# Motor_Controller_V_5_2.net
KiCad netlist of a schematic drawn in EAGLE
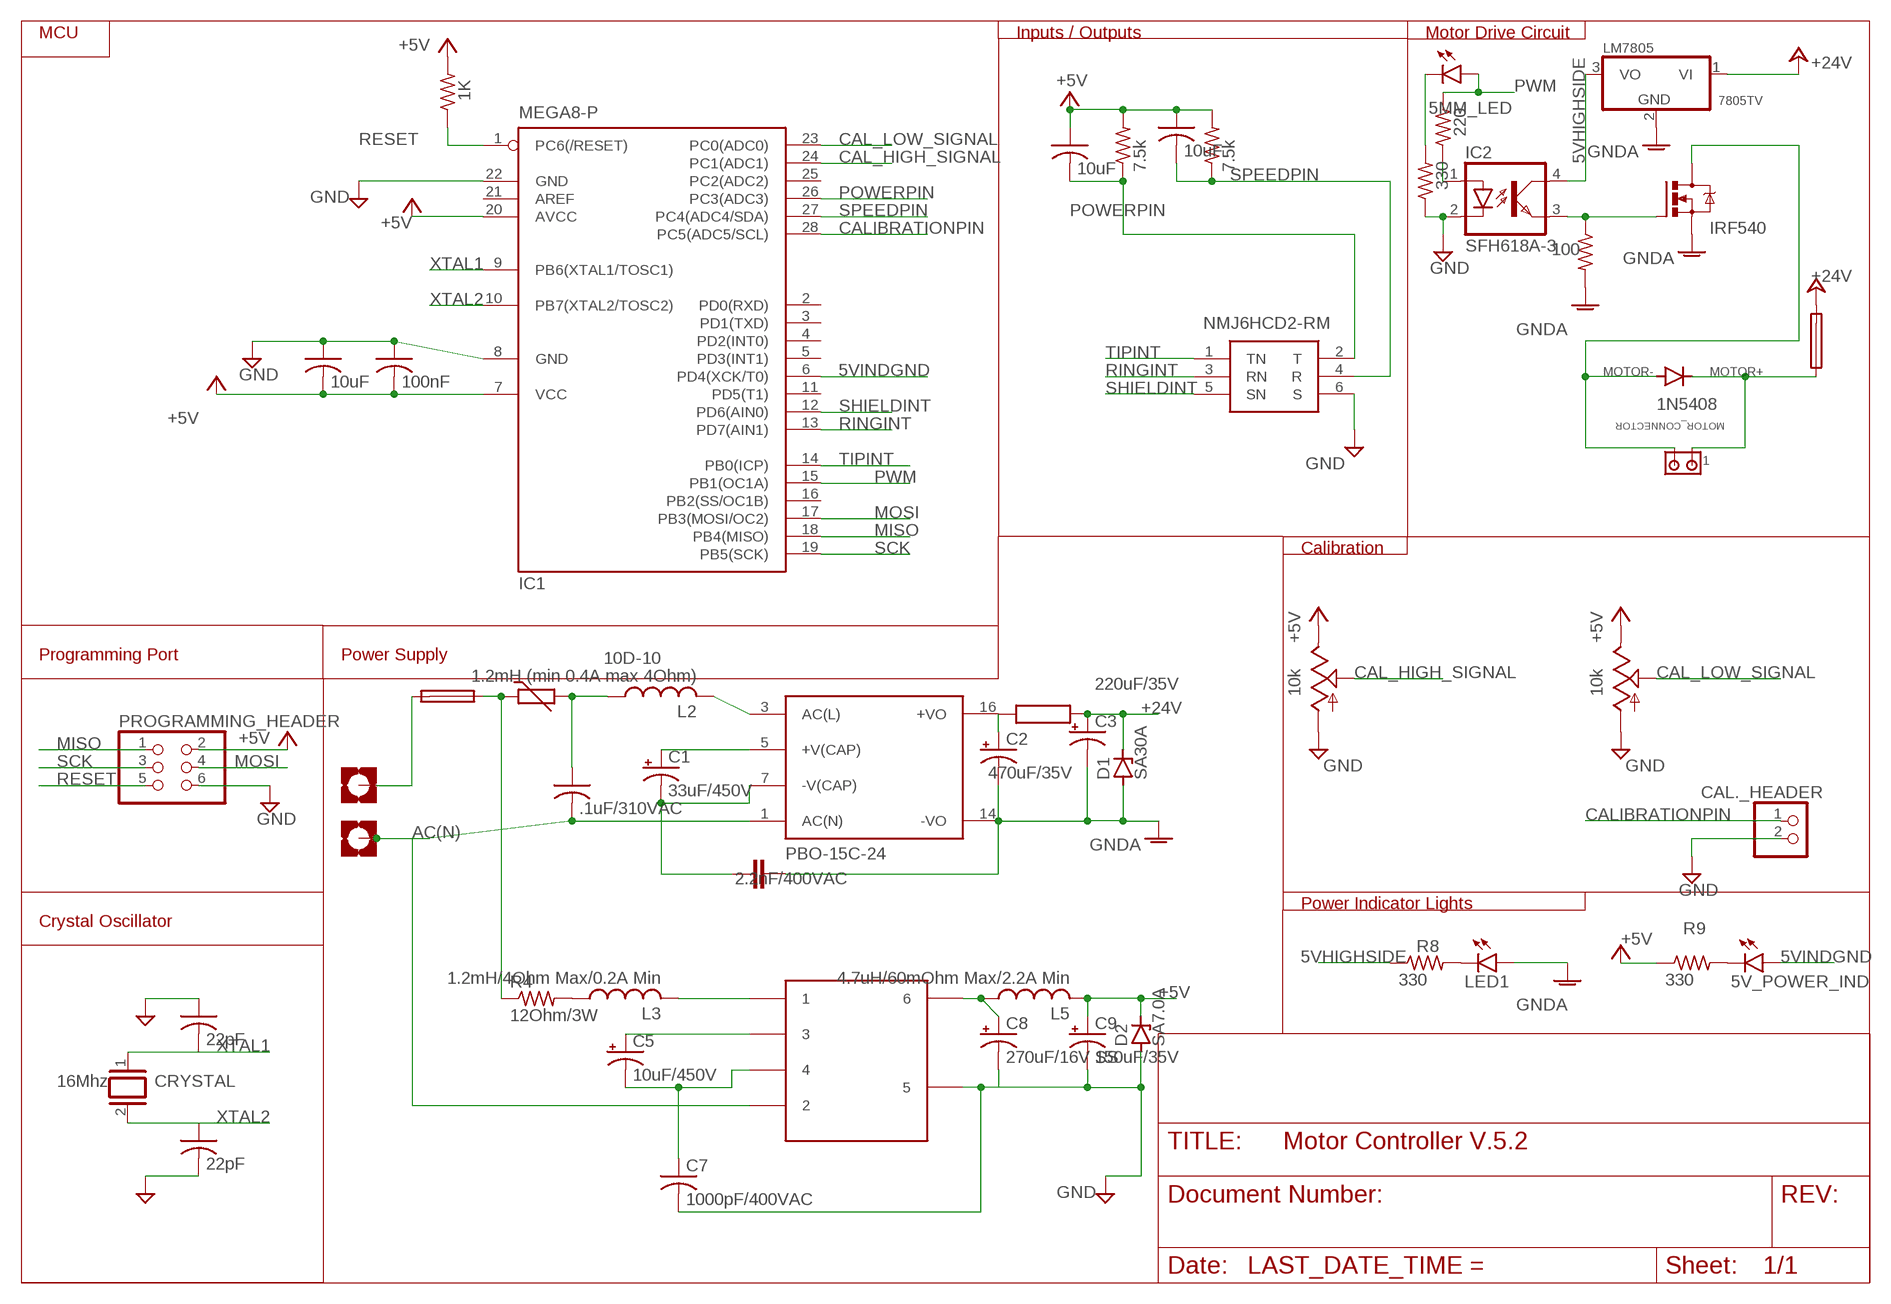
[diagram p0: schematic, sheet 1]

(export (version "E")
  (design (tool "Eeschema 10.0.6"))
  (components
    (comp (ref "5V_POWER_IND")
      (value "LED3MM")
      (footprint "eagle-import:LED3MM")
      (libsource (lib "eagle-import") (part "LED3MM"))
    )
    (comp (ref "AC(N)")
      (value "PAD3.0")
      (footprint "eagle-import:3,0-PAD-SQUARE")
      (libsource (lib "eagle-import") (part "PAD3.0"))
    )
    (comp (ref "C1")
      (value "33uF/450V")
      (footprint "eagle-import:E5-13")
      (libsource (lib "eagle-import") (part "CPOL-USE5-13"))
    )
    (comp (ref "C2")
      (value "470uF/35V")
      (footprint "eagle-import:E5-10,5")
      (fields (field (name "MF") "PANASONIC") (field (name "MPN") "ECA1VHG471B"))
      (libsource (lib "eagle-import") (part "CPOL-USE5-10.5"))
    )
    (comp (ref "C3")
      (value "220uF/35V")
      (footprint "eagle-import:E5-10,5")
      (fields (field (name "MF") "KEMET") (field (name "MPN") "A768KS227M1VLAE024"))
      (libsource (lib "eagle-import") (part "CPOL-USE5-10.5"))
    )
    (comp (ref "C4")
      (value ".1uF/310VAC")
      (footprint "eagle-import:C102-064X133")
      (libsource (lib "eagle-import") (part "CMPP_AC275V104K10S6"))
    )
    (comp (ref "C5")
      (value "10uF/450V")
      (footprint "eagle-import:E5-10,5")
      (libsource (lib "eagle-import") (part "CPOL-USE5-10.5"))
    )
    (comp (ref "C6")
      (value "22pF")
      (footprint "eagle-import:C025-024X044")
      (libsource (lib "eagle-import") (part "C-US025-024X044"))
    )
    (comp (ref "C7")
      (value "1000pF/400VAC")
      (footprint "eagle-import:C075-052X106")
      (libsource (lib "eagle-import") (part "C-US075-052X106"))
    )
    (comp (ref "C8")
      (value "270uF/16V SS")
      (footprint "eagle-import:E2,5-6")
      (libsource (lib "eagle-import") (part "CPOL-USE2.5-6"))
    )
    (comp (ref "C9")
      (value "150uF/35V")
      (footprint "eagle-import:E3,5-8")
      (libsource (lib "eagle-import") (part "CPOL-USE3.5-8"))
    )
    (comp (ref "C10")
      (value "10uF")
      (footprint "eagle-import:C025-024X044")
      (libsource (lib "eagle-import") (part "C-US025-024X044"))
    )
    (comp (ref "C12")
      (value "10uF")
      (footprint "eagle-import:C025-024X044")
      (libsource (lib "eagle-import") (part "C-US025-024X044"))
    )
    (comp (ref "C13")
      (value "10uF")
      (footprint "eagle-import:C025-024X044")
      (libsource (lib "eagle-import") (part "C-US025-024X044"))
    )
    (comp (ref "C14")
      (value "100nF")
      (footprint "eagle-import:C025-024X044")
      (libsource (lib "eagle-import") (part "C-US025-024X044"))
    )
    (comp (ref "C15")
      (value "22pF")
      (footprint "eagle-import:C025-024X044")
      (libsource (lib "eagle-import") (part "C-US025-024X044"))
    )
    (comp (ref "CAL._HEADER")
      (value "PINHD-1X2")
      (footprint "eagle-import:1X02")
      (libsource (lib "eagle-import") (part "PINHD-1X2"))
    )
    (comp (ref "CRYSTAL")
      (value "16Mhz")
      (footprint "eagle-import:QS")
      (libsource (lib "eagle-import") (part "XTAL/S"))
    )
    (comp (ref "CY1")
      (value "2.2nF/400VAC")
      (footprint "eagle-import:YC10B4")
      (libsource (lib "eagle-import") (part "CYYC10B4"))
    )
    (comp (ref "D1")
      (value "SA30A")
      (footprint "eagle-import:TVS-10")
      (libsource (lib "eagle-import") (part "TVSDIO"))
    )
    (comp (ref "D2")
      (value "SA7.0A")
      (footprint "eagle-import:TVS-10")
      (libsource (lib "eagle-import") (part "TVSDIO"))
    )
    (comp (ref "D3")
      (value "1N5408")
      (footprint "eagle-import:DO201-15")
      (fields (field (name "MF") "VISHAY") (field (name "MPN") "1N5408-E3/54"))
      (libsource (lib "eagle-import") (part "1N5400"))
    )
    (comp (ref "F1")
      (value "FUSESH22,5")
      (footprint "eagle-import:SH22,5")
      (libsource (lib "eagle-import") (part "FUSESH22,5"))
    )
    (comp (ref "F2")
      (value "1A/300V")
      (footprint "eagle-import:SH22,5")
      (libsource (lib "eagle-import") (part "FUSESH22,5"))
    )
    (comp (ref "FAST")
      (value "10k")
      (footprint "eagle-import:CT6")
      (libsource (lib "eagle-import") (part "TRIM_US-CT6"))
    )
    (comp (ref "H1")
      (value "PAD3.0")
      (footprint "eagle-import:3,0-PAD-SQUARE")
      (libsource (lib "eagle-import") (part "PAD3.0"))
    )
    (comp (ref "IC1")
      (value "MEGA8-P")
      (footprint "eagle-import:DIL28-3")
      (libsource (lib "eagle-import") (part "MEGA8-P"))
    )
    (comp (ref "IC2")
      (value "SFH618A-3")
      (footprint "eagle-import:DIP4")
      (fields (field (name "MF") "VISHAY/TELEFUNKEN"))
      (libsource (lib "eagle-import") (part "SFH618?A-3"))
    )
    (comp (ref "J1")
      (value "NMJ6HCD2-RM")
      (footprint "eagle-import:NMJ6HCD2RM")
      (fields (field (name "MOUSER_PART_NUMBER") "568-NMJ6HCD2-RM"))
      (libsource (lib "eagle-import") (part "NMJ6HCD2-RM"))
    )
    (comp (ref "L2")
      (value "1.2mH (min 0.4A max 4Ohm)")
      (footprint "eagle-import:RCP1317_INDUCTOR")
      (libsource (lib "eagle-import") (part "RCP_1317_INDUCTOR"))
    )
    (comp (ref "L3")
      (value "1.2mH/4Ohm Max/0.2A Min")
      (footprint "eagle-import:RCP1317_INDUCTOR")
      (libsource (lib "eagle-import") (part "RCP_1317_INDUCTOR"))
    )
    (comp (ref "L5")
      (value "4.7uH/60mOhm Max/2.2A Min")
      (footprint "eagle-import:RLB0914_INDUCTOR")
      (libsource (lib "eagle-import") (part "RLB0914_INDUCTOR"))
    )
    (comp (ref "LED1")
      (value "LED3MM")
      (footprint "eagle-import:LED3MM")
      (libsource (lib "eagle-import") (part "LED3MM"))
    )
    (comp (ref "LM7805")
      (value "7805TV")
      (footprint "eagle-import:TO220V")
      (libsource (lib "eagle-import") (part "78TV05"))
    )
    (comp (ref "MOTOR_CONNECTOR")
      (value "MATE-N-LOK_193839-1")
      (footprint "eagle-import:MATE-N-LOK_2PIN_CONNECTOR")
      (libsource (lib "eagle-import") (part "MATE-N-LOK_193839-1"))
    )
    (comp (ref "PROGRAMMING_HEADER")
      (value "PINHD-2X3")
      (footprint "eagle-import:2X03")
      (libsource (lib "eagle-import") (part "PINHD-2X3"))
    )
    (comp (ref "PS1")
      (value "PBO-15C-24")
      (footprint "eagle-import:CONV_PBO-15C-24")
      (fields (field (name "MF") "CUI Inc."))
      (libsource (lib "eagle-import") (part "PBO-15C-24"))
    )
    (comp (ref "PWM_IND")
      (value "5MM_LED")
      (footprint "eagle-import:5MM_LED")
      (libsource (lib "eagle-import") (part "5MM_LED"))
    )
    (comp (ref "Q1")
      (value "IRF540")
      (footprint "eagle-import:TO220BV")
      (libsource (lib "eagle-import") (part "IRF540"))
    )
    (comp (ref "R1")
      (value "10D-10")
      (footprint "eagle-import:R-7,5")
      (libsource (lib "eagle-import") (part "THERMISTOR-7,5"))
    )
    (comp (ref "R2")
      (value "1K")
      (footprint "eagle-import:0204_7")
      (libsource (lib "eagle-import") (part "R-US_0204/7"))
    )
    (comp (ref "R3")
      (value "7.5k")
      (footprint "eagle-import:0204_7")
      (libsource (lib "eagle-import") (part "R-US_0204/7"))
    )
    (comp (ref "R4")
      (value "12Ohm/3W")
      (footprint "eagle-import:VTA52")
      (libsource (lib "eagle-import") (part "BIGRESISTOR"))
    )
    (comp (ref "R5")
      (value "220")
      (footprint "eagle-import:0204_7")
      (libsource (lib "eagle-import") (part "R-US_0204/7"))
    )
    (comp (ref "R6")
      (value "100")
      (footprint "eagle-import:0204_7")
      (libsource (lib "eagle-import") (part "R-US_0204/7"))
    )
    (comp (ref "R7")
      (value "7.5k")
      (footprint "eagle-import:0204_7")
      (libsource (lib "eagle-import") (part "R-US_0204/7"))
    )
    (comp (ref "R8")
      (value "330")
      (footprint "eagle-import:0204_7")
      (libsource (lib "eagle-import") (part "R-US_0204/7"))
    )
    (comp (ref "R9")
      (value "330")
      (footprint "eagle-import:0204_7")
      (libsource (lib "eagle-import") (part "R-US_0204/7"))
    )
    (comp (ref "R10")
      (value "330")
      (footprint "eagle-import:0204_7")
      (libsource (lib "eagle-import") (part "R-US_0204/7"))
    )
    (comp (ref "SLOW")
      (value "10k")
      (footprint "eagle-import:CT6")
      (libsource (lib "eagle-import") (part "TRIM_US-CT6"))
    )
    (comp (ref "U$1")
      (value "L503-13B05R")
      (footprint "eagle-import:LS03-13BO5R3")
      (libsource (lib "eagle-import") (part "L503-13B05R"))
    )
    (comp (ref "U$2")
      (value "HCTI-22-16.4")
      (footprint "eagle-import:HCTI-22-16.4")
      (libsource (lib "eagle-import") (part "HCTI-22-16.4"))
    )
  )
  (nets
    (net (code "1") (name "+5V") (class "Default")
      (node (ref "C10") (pin "1") (pinfunction "1_1") (pintype "passive"))
      (node (ref "C12") (pin "1") (pinfunction "1_1") (pintype "passive"))
      (node (ref "C13") (pin "2") (pinfunction "2_2") (pintype "passive"))
      (node (ref "C14") (pin "2") (pinfunction "2_2") (pintype "passive"))
      (node (ref "C9") (pin "+") (pinfunction "+_+") (pintype "passive"))
      (node (ref "D2") (pin "C") (pinfunction "C_C") (pintype "passive"))
      (node (ref "FAST") (pin "E") (pinfunction "E_E") (pintype "passive"))
      (node (ref "IC1") (pin "20") (pinfunction "AVCC_20") (pintype "power_in"))
      (node (ref "IC1") (pin "7") (pinfunction "VCC_7") (pintype "power_in"))
      (node (ref "L5") (pin "P$2") (pinfunction "2_P$2") (pintype "passive"))
      (node (ref "PROGRAMMING_HEADER") (pin "2") (pinfunction "2_2") (pintype "passive"))
      (node (ref "R2") (pin "2") (pinfunction "2_2") (pintype "passive"))
      (node (ref "R3") (pin "2") (pinfunction "2_2") (pintype "passive"))
      (node (ref "R7") (pin "2") (pinfunction "2_2") (pintype "passive"))
      (node (ref "R9") (pin "1") (pinfunction "1_1") (pintype "passive"))
      (node (ref "SLOW") (pin "E") (pinfunction "E_E") (pintype "passive"))
    )
    (net (code "2") (name "+24V") (class "Default")
      (node (ref "C3") (pin "+") (pinfunction "+_+") (pintype "passive"))
      (node (ref "D1") (pin "C") (pinfunction "C_C") (pintype "passive"))
      (node (ref "F1") (pin "2") (pinfunction "2_2") (pintype "passive"))
      (node (ref "LM7805") (pin "1") (pinfunction "VI_1") (pintype "input"))
      (node (ref "U$2") (pin "P$2") (pinfunction "P$2_P$2") (pintype "bidirectional"))
    )
    (net (code "3") (name "/5VHIGHSIDE") (class "Default")
      (node (ref "IC2") (pin "4") (pinfunction "COL_4") (pintype "passive"))
      (node (ref "LM7805") (pin "3") (pinfunction "VO_3") (pintype "passive"))
      (node (ref "R8") (pin "1") (pinfunction "1_1") (pintype "passive"))
    )
    (net (code "4") (name "/5VINDGND") (class "Default")
      (node (ref "5V_POWER_IND") (pin "A") (pinfunction "A_A") (pintype "passive"))
      (node (ref "IC1") (pin "6") (pinfunction "PD4(XCK/T0)_6") (pintype "bidirectional"))
    )
    (net (code "5") (name "/AC(N)") (class "Default")
      (node (ref "AC(N)") (pin "B3,0") (pinfunction "MOUNT_B3,0") (pintype "passive"))
      (node (ref "C4") (pin "2") (pinfunction "2_2") (pintype "passive"))
      (node (ref "PS1") (pin "1") (pinfunction "AC(N)_1") (pintype "input"))
      (node (ref "U$1") (pin "3") (pinfunction "2_3") (pintype "bidirectional"))
      (node (ref "U$1") (pin "4") (pinfunction "2_4") (pintype "bidirectional"))
    )
    (net (code "6") (name "/CALIBRATIONPIN") (class "Default")
      (node (ref "CAL._HEADER") (pin "1") (pinfunction "1_1") (pintype "passive"))
      (node (ref "IC1") (pin "28") (pinfunction "PC5(ADC5/SCL)_28") (pintype "bidirectional"))
    )
    (net (code "7") (name "/CAL_HIGH_SIGNAL") (class "Default")
      (node (ref "FAST") (pin "S") (pinfunction "S_S") (pintype "passive"))
      (node (ref "IC1") (pin "24") (pinfunction "PC1(ADC1)_24") (pintype "bidirectional"))
    )
    (net (code "8") (name "/CAL_LOW_SIGNAL") (class "Default")
      (node (ref "IC1") (pin "23") (pinfunction "PC0(ADC0)_23") (pintype "bidirectional"))
      (node (ref "SLOW") (pin "S") (pinfunction "S_S") (pintype "passive"))
    )
    (net (code "9") (name "/MISO") (class "Default")
      (node (ref "IC1") (pin "18") (pinfunction "PB4(MISO)_18") (pintype "bidirectional"))
      (node (ref "PROGRAMMING_HEADER") (pin "1") (pinfunction "1_1") (pintype "passive"))
    )
    (net (code "10") (name "/MOSI") (class "Default")
      (node (ref "IC1") (pin "17") (pinfunction "PB3(MOSI/OC2)_17") (pintype "bidirectional"))
      (node (ref "PROGRAMMING_HEADER") (pin "4") (pinfunction "4_4") (pintype "passive"))
    )
    (net (code "11") (name "/MOTOR+") (class "Default")
      (node (ref "D3") (pin "C") (pinfunction "C_C") (pintype "passive"))
      (node (ref "F1") (pin "1") (pinfunction "1_1") (pintype "passive"))
      (node (ref "MOTOR_CONNECTOR") (pin "P$1") (pinfunction "1_P$1") (pintype "passive"))
    )
    (net (code "12") (name "/MOTOR-") (class "Default")
      (node (ref "D3") (pin "A") (pinfunction "A_A") (pintype "passive"))
      (node (ref "MOTOR_CONNECTOR") (pin "P$2") (pinfunction "2_P$2") (pintype "passive"))
      (node (ref "Q1") (pin "D") (pinfunction "D_D") (pintype "passive"))
    )
    (net (code "13") (name "/POWERPIN") (class "Default")
      (node (ref "C10") (pin "2") (pinfunction "2_2") (pintype "passive"))
      (node (ref "IC1") (pin "26") (pinfunction "PC3(ADC3)_26") (pintype "bidirectional"))
      (node (ref "J1") (pin "2") (pinfunction "T_2") (pintype "bidirectional"))
      (node (ref "R3") (pin "1") (pinfunction "1_1") (pintype "passive"))
    )
    (net (code "14") (name "/PWM") (class "Default")
      (node (ref "IC1") (pin "15") (pinfunction "PB1(OC1A)_15") (pintype "bidirectional"))
      (node (ref "PWM_IND") (pin "A") (pinfunction "A_A") (pintype "passive"))
      (node (ref "R5") (pin "2") (pinfunction "2_2") (pintype "passive"))
    )
    (net (code "15") (name "/RESET") (class "Default")
      (node (ref "IC1") (pin "1") (pinfunction "PC6(/RESET)_1") (pintype "bidirectional"))
      (node (ref "PROGRAMMING_HEADER") (pin "5") (pinfunction "5_5") (pintype "passive"))
      (node (ref "R2") (pin "1") (pinfunction "1_1") (pintype "passive"))
    )
    (net (code "16") (name "/RINGINT") (class "Default")
      (node (ref "IC1") (pin "13") (pinfunction "PD7(AIN1)_13") (pintype "bidirectional"))
      (node (ref "J1") (pin "3") (pinfunction "RN_3") (pintype "bidirectional"))
    )
    (net (code "17") (name "/SCK") (class "Default")
      (node (ref "IC1") (pin "19") (pinfunction "PB5(SCK)_19") (pintype "bidirectional"))
      (node (ref "PROGRAMMING_HEADER") (pin "3") (pinfunction "3_3") (pintype "passive"))
    )
    (net (code "18") (name "/SHIELDINT") (class "Default")
      (node (ref "IC1") (pin "12") (pinfunction "PD6(AIN0)_12") (pintype "bidirectional"))
      (node (ref "J1") (pin "5") (pinfunction "SN_5") (pintype "bidirectional"))
    )
    (net (code "19") (name "/SPEEDPIN") (class "Default")
      (node (ref "C12") (pin "2") (pinfunction "2_2") (pintype "passive"))
      (node (ref "IC1") (pin "27") (pinfunction "PC4(ADC4/SDA)_27") (pintype "bidirectional"))
      (node (ref "J1") (pin "4") (pinfunction "R_4") (pintype "bidirectional"))
      (node (ref "R7") (pin "1") (pinfunction "1_1") (pintype "passive"))
    )
    (net (code "20") (name "/TIPINT") (class "Default")
      (node (ref "IC1") (pin "14") (pinfunction "PB0(ICP)_14") (pintype "bidirectional"))
      (node (ref "J1") (pin "1") (pinfunction "TN_1") (pintype "bidirectional"))
    )
    (net (code "21") (name "/XTAL1") (class "Default")
      (node (ref "C15") (pin "2") (pinfunction "2_2") (pintype "passive"))
      (node (ref "CRYSTAL") (pin "1") (pinfunction "1_1") (pintype "passive"))
      (node (ref "IC1") (pin "9") (pinfunction "PB6(XTAL1/TOSC1)_9") (pintype "bidirectional"))
    )
    (net (code "22") (name "/XTAL2") (class "Default")
      (node (ref "C6") (pin "1") (pinfunction "1_1") (pintype "passive"))
      (node (ref "CRYSTAL") (pin "2") (pinfunction "2_2") (pintype "passive"))
      (node (ref "IC1") (pin "10") (pinfunction "PB7(XTAL2/TOSC2)_10") (pintype "bidirectional"))
    )
    (net (code "23") (name "GND") (class "Default")
      (node (ref "C13") (pin "1") (pinfunction "1_1") (pintype "passive"))
      (node (ref "C14") (pin "1") (pinfunction "1_1") (pintype "passive"))
      (node (ref "C15") (pin "1") (pinfunction "1_1") (pintype "passive"))
      (node (ref "C6") (pin "2") (pinfunction "2_2") (pintype "passive"))
      (node (ref "C7") (pin "2") (pinfunction "2_2") (pintype "passive"))
      (node (ref "C8") (pin "-") (pinfunction "-_-") (pintype "passive"))
      (node (ref "C9") (pin "-") (pinfunction "-_-") (pintype "passive"))
      (node (ref "CAL._HEADER") (pin "2") (pinfunction "2_2") (pintype "passive"))
      (node (ref "D2") (pin "A") (pinfunction "A_A") (pintype "passive"))
      (node (ref "FAST") (pin "A") (pinfunction "A_A") (pintype "passive"))
      (node (ref "IC1") (pin "22") (pinfunction "GND_22") (pintype "power_in"))
      (node (ref "IC1") (pin "8") (pinfunction "GND_8") (pintype "power_in"))
      (node (ref "IC2") (pin "2") (pinfunction "C_2") (pintype "passive"))
      (node (ref "J1") (pin "6") (pinfunction "S_6") (pintype "bidirectional"))
      (node (ref "PROGRAMMING_HEADER") (pin "6") (pinfunction "6_6") (pintype "passive"))
      (node (ref "R10") (pin "1") (pinfunction "1_1") (pintype "passive"))
      (node (ref "SLOW") (pin "A") (pinfunction "A_A") (pintype "passive"))
      (node (ref "U$1") (pin "10") (pinfunction "5_10") (pintype "bidirectional"))
      (node (ref "U$1") (pin "9") (pinfunction "5_9") (pintype "bidirectional"))
    )
    (net (code "24") (name "GNDA") (class "Default")
      (node (ref "C2") (pin "-") (pinfunction "-_-") (pintype "passive"))
      (node (ref "C3") (pin "-") (pinfunction "-_-") (pintype "passive"))
      (node (ref "CY1") (pin "1") (pinfunction "1_1") (pintype "passive"))
      (node (ref "D1") (pin "A") (pinfunction "A_A") (pintype "passive"))
      (node (ref "LED1") (pin "A") (pinfunction "A_A") (pintype "passive"))
      (node (ref "LM7805") (pin "2") (pinfunction "GND_2") (pintype "passive"))
      (node (ref "PS1") (pin "14") (pinfunction "-VO_14") (pintype "output"))
      (node (ref "Q1") (pin "S") (pinfunction "S_S") (pintype "passive"))
      (node (ref "R6") (pin "2") (pinfunction "2_2") (pintype "passive"))
    )
    (net (code "25") (name "Net-(5V_POWER_IND-C)") (class "Default")
      (node (ref "5V_POWER_IND") (pin "K") (pinfunction "C_K") (pintype "passive"))
      (node (ref "R9") (pin "2") (pinfunction "2_2") (pintype "passive"))
    )
    (net (code "26") (name "Net-(C5-Pad+)") (class "Default")
      (node (ref "C5") (pin "+") (pinfunction "+_+") (pintype "passive"))
      (node (ref "U$1") (pin "5") (pinfunction "3_5") (pintype "bidirectional"))
      (node (ref "U$1") (pin "6") (pinfunction "3_6") (pintype "bidirectional"))
    )
    (net (code "27") (name "Net-(C5-Pad-)") (class "Default")
      (node (ref "C5") (pin "-") (pinfunction "-_-") (pintype "passive"))
      (node (ref "C7") (pin "1") (pinfunction "1_1") (pintype "passive"))
      (node (ref "U$1") (pin "7") (pinfunction "4_7") (pintype "bidirectional"))
      (node (ref "U$1") (pin "8") (pinfunction "4_8") (pintype "bidirectional"))
    )
    (net (code "28") (name "Net-(F2-Pad1)") (class "Default")
      (node (ref "F2") (pin "1") (pinfunction "1_1") (pintype "passive"))
      (node (ref "R1") (pin "1") (pinfunction "1_1") (pintype "passive"))
      (node (ref "R4") (pin "1") (pinfunction "1_1") (pintype "passive"))
    )
    (net (code "29") (name "Net-(H1-MOUNT)") (class "Default")
      (node (ref "F2") (pin "2") (pinfunction "2_2") (pintype "passive"))
      (node (ref "H1") (pin "B3,0") (pinfunction "MOUNT_B3,0") (pintype "passive"))
    )
    (net (code "30") (name "Net-(IC2-A)") (class "Default")
      (node (ref "IC2") (pin "1") (pinfunction "A_1") (pintype "passive"))
      (node (ref "R5") (pin "1") (pinfunction "1_1") (pintype "passive"))
    )
    (net (code "31") (name "Net-(IC2-EMIT)") (class "Default")
      (node (ref "IC2") (pin "3") (pinfunction "EMIT_3") (pintype "passive"))
      (node (ref "Q1") (pin "G") (pinfunction "G_G") (pintype "passive"))
      (node (ref "R6") (pin "1") (pinfunction "1_1") (pintype "passive"))
    )
    (net (code "32") (name "Net-(L2-1)") (class "Default")
      (node (ref "C4") (pin "1") (pinfunction "1_1") (pintype "passive"))
      (node (ref "L2") (pin "P$1") (pinfunction "1_P$1") (pintype "passive"))
      (node (ref "R1") (pin "2") (pinfunction "2_2") (pintype "passive"))
    )
    (net (code "33") (name "Net-(L2-2)") (class "Default")
      (node (ref "L2") (pin "P$2") (pinfunction "2_P$2") (pintype "passive"))
      (node (ref "PS1") (pin "3") (pinfunction "AC(L)_3") (pintype "input"))
    )
    (net (code "34") (name "Net-(L3-1)") (class "Default")
      (node (ref "L3") (pin "P$1") (pinfunction "1_P$1") (pintype "passive"))
      (node (ref "R4") (pin "2") (pinfunction "2_2") (pintype "passive"))
    )
    (net (code "35") (name "Net-(L3-2)") (class "Default")
      (node (ref "L3") (pin "P$2") (pinfunction "2_P$2") (pintype "passive"))
      (node (ref "U$1") (pin "1") (pinfunction "1_1") (pintype "bidirectional"))
      (node (ref "U$1") (pin "2") (pinfunction "1_2") (pintype "bidirectional"))
    )
    (net (code "36") (name "Net-(L5-1)") (class "Default")
      (node (ref "C8") (pin "+") (pinfunction "+_+") (pintype "passive"))
      (node (ref "L5") (pin "P$1") (pinfunction "1_P$1") (pintype "passive"))
      (node (ref "U$1") (pin "11") (pinfunction "6_11") (pintype "bidirectional"))
      (node (ref "U$1") (pin "12") (pinfunction "6_12") (pintype "bidirectional"))
    )
    (net (code "37") (name "Net-(LED1-C)") (class "Default")
      (node (ref "LED1") (pin "K") (pinfunction "C_K") (pintype "passive"))
      (node (ref "R8") (pin "2") (pinfunction "2_2") (pintype "passive"))
    )
    (net (code "38") (name "Net-(PS1-+V(CAP))") (class "Default")
      (node (ref "C1") (pin "+") (pinfunction "+_+") (pintype "passive"))
      (node (ref "PS1") (pin "5") (pinfunction "+V(CAP)_5") (pintype "passive"))
    )
    (net (code "39") (name "Net-(PS1-+VO)") (class "Default")
      (node (ref "C2") (pin "+") (pinfunction "+_+") (pintype "passive"))
      (node (ref "PS1") (pin "16") (pinfunction "+VO_16") (pintype "output"))
      (node (ref "U$2") (pin "P$1") (pinfunction "P$1_P$1") (pintype "bidirectional"))
    )
    (net (code "40") (name "Net-(PS1--V(CAP))") (class "Default")
      (node (ref "C1") (pin "-") (pinfunction "-_-") (pintype "passive"))
      (node (ref "CY1") (pin "2") (pinfunction "2_2") (pintype "passive"))
      (node (ref "PS1") (pin "7") (pinfunction "-V(CAP)_7") (pintype "passive"))
    )
    (net (code "41") (name "Net-(PWM_IND-PadC)") (class "Default")
      (node (ref "PWM_IND") (pin "C") (pinfunction "C_C") (pintype "passive"))
      (node (ref "R10") (pin "2") (pinfunction "2_2") (pintype "passive"))
    )
    (net (code "42") (name "unconnected-(IC1-AREF-Pad21)") (class "Default")
      (node (ref "IC1") (pin "21") (pinfunction "AREF_21") (pintype "passive"))
    )
    (net (code "43") (name "unconnected-(IC1-PB2(SS{slash}OC1B)-Pad16)") (class "Default")
      (node (ref "IC1") (pin "16") (pinfunction "PB2(SS/OC1B)_16") (pintype "bidirectional"))
    )
    (net (code "44") (name "unconnected-(IC1-PC2(ADC2)-Pad25)") (class "Default")
      (node (ref "IC1") (pin "25") (pinfunction "PC2(ADC2)_25") (pintype "bidirectional"))
    )
    (net (code "45") (name "unconnected-(IC1-PD0(RXD)-Pad2)") (class "Default")
      (node (ref "IC1") (pin "2") (pinfunction "PD0(RXD)_2") (pintype "bidirectional"))
    )
    (net (code "46") (name "unconnected-(IC1-PD1(TXD)-Pad3)") (class "Default")
      (node (ref "IC1") (pin "3") (pinfunction "PD1(TXD)_3") (pintype "bidirectional"))
    )
    (net (code "47") (name "unconnected-(IC1-PD2(INT0)-Pad4)") (class "Default")
      (node (ref "IC1") (pin "4") (pinfunction "PD2(INT0)_4") (pintype "bidirectional"))
    )
    (net (code "48") (name "unconnected-(IC1-PD3(INT1)-Pad5)") (class "Default")
      (node (ref "IC1") (pin "5") (pinfunction "PD3(INT1)_5") (pintype "bidirectional"))
    )
    (net (code "49") (name "unconnected-(IC1-PD5(T1)-Pad11)") (class "Default")
      (node (ref "IC1") (pin "11") (pinfunction "PD5(T1)_11") (pintype "bidirectional"))
    )
  )
)
